# Board_3.net
KiCad netlist of a schematic drawn in EAGLE
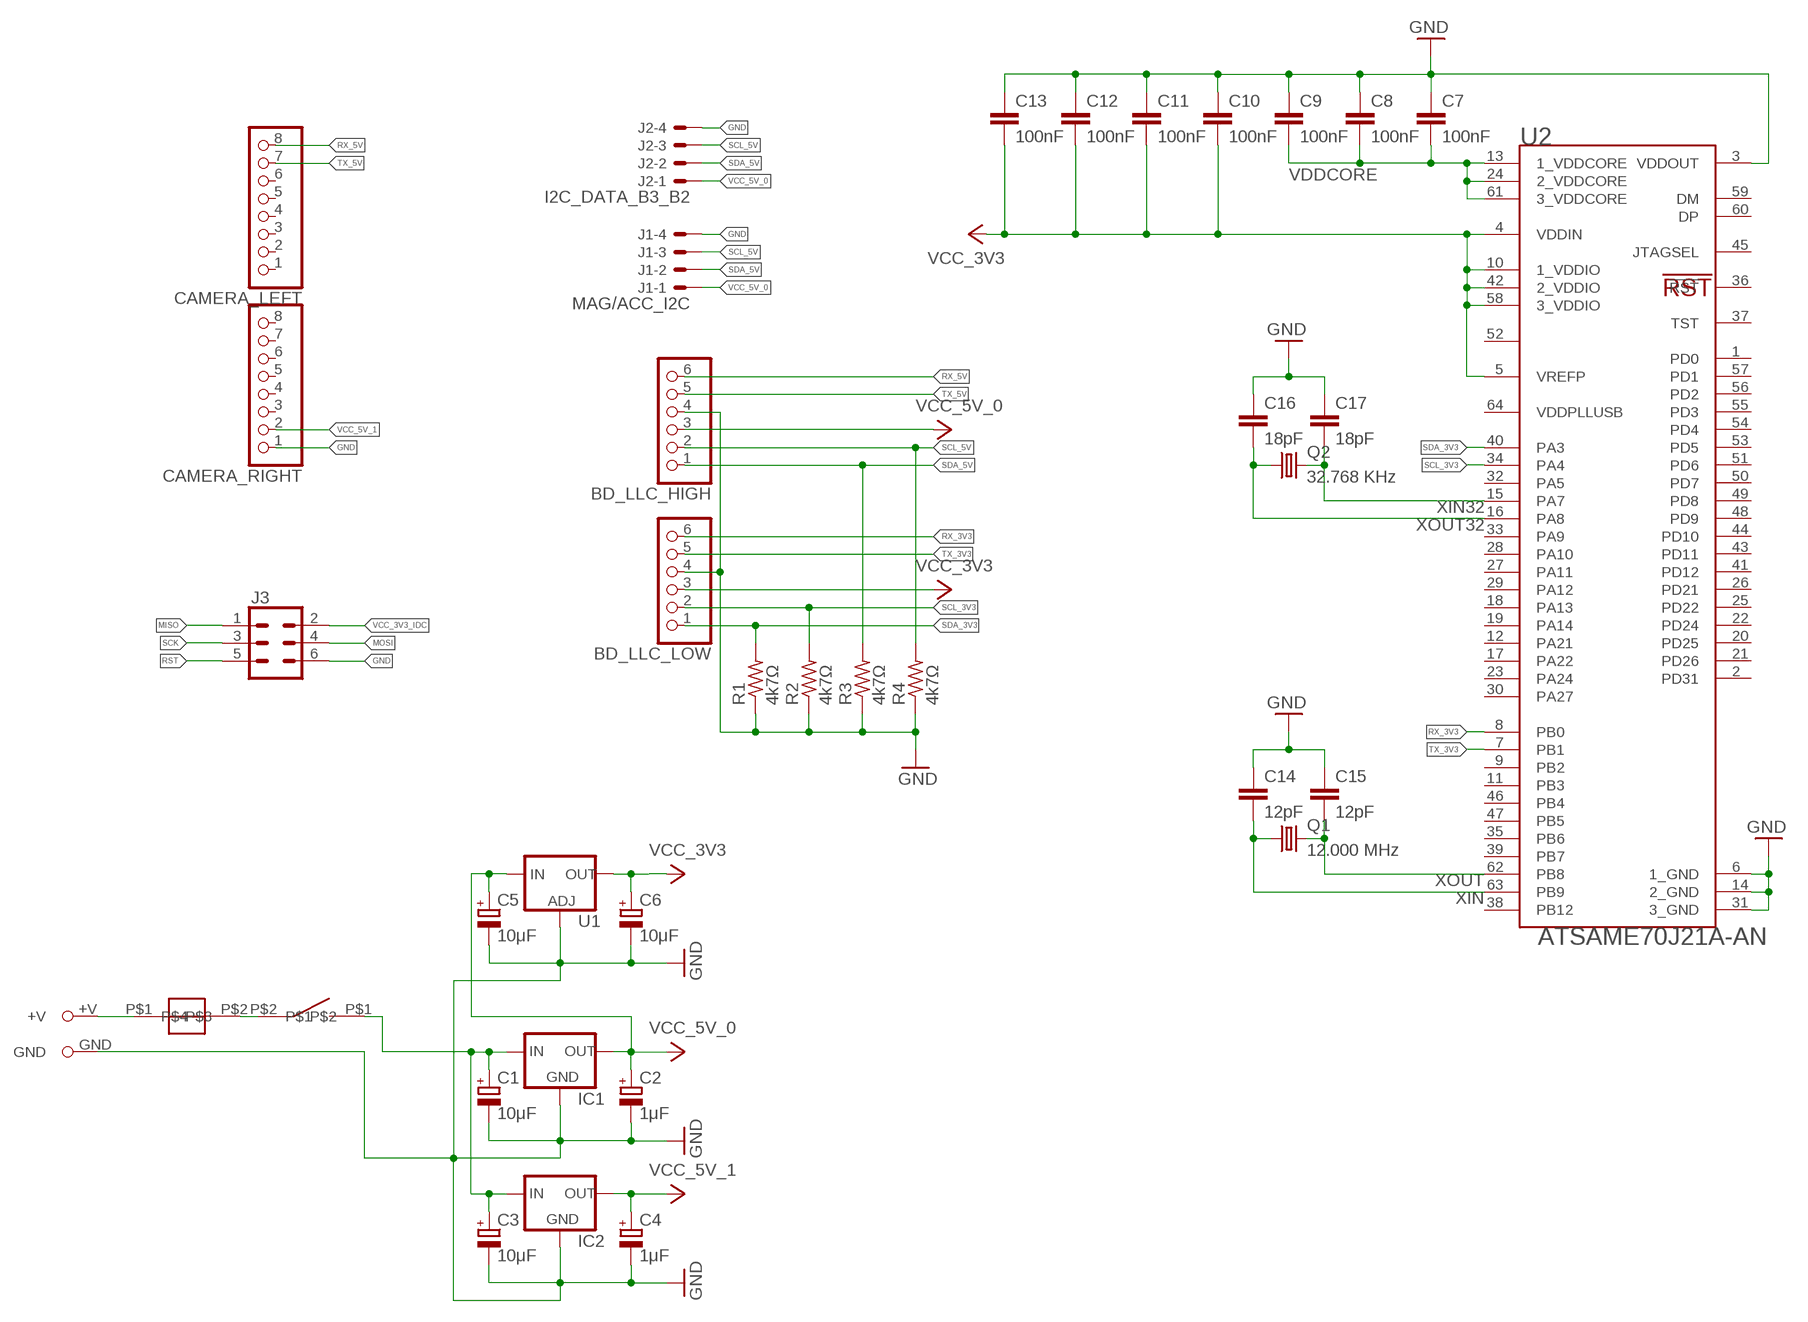
[diagram p0: schematic, sheet 1]

(export (version "E")
  (design (tool "Eeschema 10.0.6"))
  (components
    (comp (ref "BD_LLC_HIGH")
      (value "PINHD-1X6")
      (footprint "eagle-import:1X06")
      (libsource (lib "eagle-import") (part "PINHD-1X6"))
    )
    (comp (ref "BD_LLC_LOW")
      (value "PINHD-1X6")
      (footprint "eagle-import:1X06")
      (libsource (lib "eagle-import") (part "PINHD-1X6"))
    )
    (comp (ref "C1")
      (value "10μF")
      (footprint "eagle-import:E2-5")
      (libsource (lib "eagle-import") (part "CPOL-EUE2-5"))
    )
    (comp (ref "C2")
      (value "1μF")
      (footprint "eagle-import:E2-5")
      (libsource (lib "eagle-import") (part "CPOL-EUE2-5"))
    )
    (comp (ref "C3")
      (value "10μF")
      (footprint "eagle-import:E2-5")
      (libsource (lib "eagle-import") (part "CPOL-EUE2-5"))
    )
    (comp (ref "C4")
      (value "1μF")
      (footprint "eagle-import:E2-5")
      (libsource (lib "eagle-import") (part "CPOL-EUE2-5"))
    )
    (comp (ref "C5")
      (value "10μF")
      (footprint "eagle-import:E2-5")
      (libsource (lib "eagle-import") (part "CPOL-EUE2-5"))
    )
    (comp (ref "C6")
      (value "10μF")
      (footprint "eagle-import:E2-5")
      (libsource (lib "eagle-import") (part "CPOL-EUE2-5"))
    )
    (comp (ref "C7")
      (value "100nF")
      (footprint "eagle-import:C050-024X044")
      (libsource (lib "eagle-import") (part "C-EU050-024X044"))
    )
    (comp (ref "C8")
      (value "100nF")
      (footprint "eagle-import:C050-024X044")
      (libsource (lib "eagle-import") (part "C-EU050-024X044"))
    )
    (comp (ref "C9")
      (value "100nF")
      (footprint "eagle-import:C050-024X044")
      (libsource (lib "eagle-import") (part "C-EU050-024X044"))
    )
    (comp (ref "C10")
      (value "100nF")
      (footprint "eagle-import:C050-024X044")
      (libsource (lib "eagle-import") (part "C-EU050-024X044"))
    )
    (comp (ref "C11")
      (value "100nF")
      (footprint "eagle-import:C050-024X044")
      (libsource (lib "eagle-import") (part "C-EU050-024X044"))
    )
    (comp (ref "C12")
      (value "100nF")
      (footprint "eagle-import:C050-024X044")
      (libsource (lib "eagle-import") (part "C-EU050-024X044"))
    )
    (comp (ref "C13")
      (value "100nF")
      (footprint "eagle-import:C050-024X044")
      (libsource (lib "eagle-import") (part "C-EU050-024X044"))
    )
    (comp (ref "C14")
      (value "12pF")
      (footprint "eagle-import:C050-024X044")
      (libsource (lib "eagle-import") (part "C-EU050-024X044"))
    )
    (comp (ref "C15")
      (value "12pF")
      (footprint "eagle-import:C050-024X044")
      (libsource (lib "eagle-import") (part "C-EU050-024X044"))
    )
    (comp (ref "C16")
      (value "18pF")
      (footprint "eagle-import:C050-024X044")
      (libsource (lib "eagle-import") (part "C-EU050-024X044"))
    )
    (comp (ref "C17")
      (value "18pF")
      (footprint "eagle-import:C050-024X044")
      (libsource (lib "eagle-import") (part "C-EU050-024X044"))
    )
    (comp (ref "CAMERA_LEFT")
      (value "PINHD-1X8")
      (footprint "eagle-import:1X08")
      (libsource (lib "eagle-import") (part "PINHD-1X8"))
    )
    (comp (ref "CAMERA_RIGHT")
      (value "PINHD-1X8")
      (footprint "eagle-import:1X08")
      (libsource (lib "eagle-import") (part "PINHD-1X8"))
    )
    (comp (ref "IC1")
      (value "78XXS")
      (footprint "eagle-import:78XXS")
      (libsource (lib "eagle-import") (part "78XXS"))
    )
    (comp (ref "IC2")
      (value "78XXS")
      (footprint "eagle-import:78XXS")
      (libsource (lib "eagle-import") (part "78XXS"))
    )
    (comp (ref "J1")
      (value "MAG/ACC_I2C")
      (footprint "eagle-import:6410-04")
      (fields (field (name "MF") "MOLEX"))
      (libsource (lib "eagle-import") (part "22-?-0427-2041"))
    )
    (comp (ref "J2")
      (value "I2C_DATA_B3_B2")
      (footprint "eagle-import:6410-04")
      (fields (field (name "MF") "MOLEX"))
      (libsource (lib "eagle-import") (part "22-?-0427-2041"))
    )
    (comp (ref "J3")
      (value "CONN_03X2SHROUD")
      (footprint "eagle-import:2X3-SHROUDED")
      (libsource (lib "eagle-import") (part "CONN_03X2SHROUD"))
    )
    (comp (ref "Q1")
      (value "12.000 MHz")
      (footprint "eagle-import:HC49U-V")
      (libsource (lib "eagle-import") (part "crystal_204_CRYSTALHC49U-V"))
    )
    (comp (ref "Q2")
      (value "32.768 KHz")
      (footprint "eagle-import:TC26V")
      (libsource (lib "eagle-import") (part "CRYSTALTC26V"))
    )
    (comp (ref "R1")
      (value "4k7Ω")
      (footprint "eagle-import:0207_10")
      (libsource (lib "eagle-import") (part "R-US_0207/10"))
    )
    (comp (ref "R2")
      (value "4k7Ω")
      (footprint "eagle-import:0207_10")
      (libsource (lib "eagle-import") (part "R-US_0207/10"))
    )
    (comp (ref "R3")
      (value "4k7Ω")
      (footprint "eagle-import:0207_10")
      (libsource (lib "eagle-import") (part "R-US_0207/10"))
    )
    (comp (ref "R4")
      (value "4k7Ω")
      (footprint "eagle-import:0207_10")
      (libsource (lib "eagle-import") (part "R-US_0207/10"))
    )
    (comp (ref "SICHERUNG1")
      (value "SICHERUNG")
      (footprint "eagle-import:SICHERUNG")
      (libsource (lib "eagle-import") (part "SICHERUNG"))
    )
    (comp (ref "U$1")
      (value "XT60")
      (footprint "eagle-import:XT60")
      (libsource (lib "eagle-import") (part "XT60"))
    )
    (comp (ref "U$17")
      (value "SCHALTER")
      (footprint "eagle-import:SCHALTER")
      (libsource (lib "eagle-import") (part "SCHALTER"))
    )
    (comp (ref "U1")
      (value "V_REG_LM1117SOT223")
      (footprint "eagle-import:SOT223")
      (libsource (lib "eagle-import") (part "V_REG_LM1117SOT223"))
    )
    (comp (ref "U2")
      (value "ATMEL_CORPORATION_ATSAME70J21A-ANATMEL_CORPORATION_ATSAME70J21A-AN_0_0")
      (footprint "eagle-import:ATMEL_CORPORATION_ATSAME70J21A-AN_0")
      (fields
        (field (name "DIGIKEY_PART_NUMBER") "ATSAME70J21A-AN-ND")
        (field (name "MF") "Atmel Corporation")
        (field (name "MOUSER_PART_NUMBER") "556-ATSAME70J21A-AN")
      )
      (libsource (lib "eagle-import") (part "ATMEL_CORPORATION_ATSAME70J21A-ANATMEL_CORPORATION_ATSAME70J21A-AN_0_0"))
    )
  )
  (nets
    (net (code "1") (name "/VDDCORE") (class "Default")
      (node (ref "C7") (pin "2") (pinfunction "2_2") (pintype "passive"))
      (node (ref "C8") (pin "2") (pinfunction "2_2") (pintype "passive"))
      (node (ref "C9") (pin "2") (pinfunction "2_2") (pintype "passive"))
      (node (ref "U2") (pin "13") (pinfunction "1_VDDCORE_13") (pintype "bidirectional"))
      (node (ref "U2") (pin "24") (pinfunction "2_VDDCORE_24") (pintype "bidirectional"))
      (node (ref "U2") (pin "61") (pinfunction "3_VDDCORE_61") (pintype "bidirectional"))
    )
    (net (code "2") (name "/XIN") (class "Default")
      (node (ref "C14") (pin "2") (pinfunction "2_2") (pintype "passive"))
      (node (ref "Q1") (pin "1") (pinfunction "1_1") (pintype "passive"))
      (node (ref "U2") (pin "63") (pinfunction "PB9_63") (pintype "bidirectional"))
    )
    (net (code "3") (name "/XIN32") (class "Default")
      (node (ref "C17") (pin "2") (pinfunction "2_2") (pintype "passive"))
      (node (ref "Q2") (pin "2") (pinfunction "2_2") (pintype "passive"))
      (node (ref "U2") (pin "15") (pinfunction "PA7_15") (pintype "bidirectional"))
    )
    (net (code "4") (name "/XOUT") (class "Default")
      (node (ref "C15") (pin "2") (pinfunction "2_2") (pintype "passive"))
      (node (ref "Q1") (pin "2") (pinfunction "2_2") (pintype "passive"))
      (node (ref "U2") (pin "62") (pinfunction "PB8_62") (pintype "bidirectional"))
    )
    (net (code "5") (name "/XOUT32") (class "Default")
      (node (ref "C16") (pin "2") (pinfunction "2_2") (pintype "passive"))
      (node (ref "Q2") (pin "1") (pinfunction "1_1") (pintype "passive"))
      (node (ref "U2") (pin "16") (pinfunction "PA8_16") (pintype "bidirectional"))
    )
    (net (code "6") (name "GND") (class "Default")
      (node (ref "BD_LLC_HIGH") (pin "4") (pinfunction "4_4") (pintype "passive"))
      (node (ref "BD_LLC_LOW") (pin "4") (pinfunction "4_4") (pintype "passive"))
      (node (ref "C1") (pin "-") (pinfunction "-_-") (pintype "passive"))
      (node (ref "C10") (pin "1") (pinfunction "1_1") (pintype "passive"))
      (node (ref "C11") (pin "1") (pinfunction "1_1") (pintype "passive"))
      (node (ref "C12") (pin "1") (pinfunction "1_1") (pintype "passive"))
      (node (ref "C13") (pin "1") (pinfunction "1_1") (pintype "passive"))
      (node (ref "C14") (pin "1") (pinfunction "1_1") (pintype "passive"))
      (node (ref "C15") (pin "1") (pinfunction "1_1") (pintype "passive"))
      (node (ref "C16") (pin "1") (pinfunction "1_1") (pintype "passive"))
      (node (ref "C17") (pin "1") (pinfunction "1_1") (pintype "passive"))
      (node (ref "C2") (pin "-") (pinfunction "-_-") (pintype "passive"))
      (node (ref "C3") (pin "-") (pinfunction "-_-") (pintype "passive"))
      (node (ref "C4") (pin "-") (pinfunction "-_-") (pintype "passive"))
      (node (ref "C5") (pin "-") (pinfunction "-_-") (pintype "passive"))
      (node (ref "C6") (pin "-") (pinfunction "-_-") (pintype "passive"))
      (node (ref "C7") (pin "1") (pinfunction "1_1") (pintype "passive"))
      (node (ref "C8") (pin "1") (pinfunction "1_1") (pintype "passive"))
      (node (ref "C9") (pin "1") (pinfunction "1_1") (pintype "passive"))
      (node (ref "CAMERA_RIGHT") (pin "1") (pinfunction "1_1") (pintype "passive"))
      (node (ref "IC1") (pin "GND") (pinfunction "GND_GND") (pintype "input"))
      (node (ref "IC2") (pin "GND") (pinfunction "GND_GND") (pintype "input"))
      (node (ref "J1") (pin "4") (pinfunction "S_4") (pintype "passive"))
      (node (ref "J2") (pin "4") (pinfunction "S_4") (pintype "passive"))
      (node (ref "J3") (pin "6") (pinfunction "6_6") (pintype "bidirectional"))
      (node (ref "R1") (pin "1") (pinfunction "1_1") (pintype "passive"))
      (node (ref "R2") (pin "1") (pinfunction "1_1") (pintype "passive"))
      (node (ref "R3") (pin "1") (pinfunction "1_1") (pintype "passive"))
      (node (ref "R4") (pin "1") (pinfunction "1_1") (pintype "passive"))
      (node (ref "U$1") (pin "GND") (pinfunction "GND_GND") (pintype "bidirectional"))
      (node (ref "U1") (pin "1") (pinfunction "ADJ_1") (pintype "input"))
      (node (ref "U2") (pin "14") (pinfunction "2_GND_14") (pintype "bidirectional"))
      (node (ref "U2") (pin "3") (pinfunction "VDDOUT_3") (pintype "bidirectional"))
      (node (ref "U2") (pin "31") (pinfunction "3_GND_31") (pintype "bidirectional"))
      (node (ref "U2") (pin "6") (pinfunction "1_GND_6") (pintype "bidirectional"))
    )
    (net (code "7") (name "MISO") (class "Default")
      (node (ref "J3") (pin "1") (pinfunction "1_1") (pintype "bidirectional"))
    )
    (net (code "8") (name "MOSI") (class "Default")
      (node (ref "J3") (pin "4") (pinfunction "4_4") (pintype "bidirectional"))
    )
    (net (code "9") (name "Net-(C1-Pad+)") (class "Default")
      (node (ref "C1") (pin "+") (pinfunction "+_+") (pintype "passive"))
      (node (ref "C3") (pin "+") (pinfunction "+_+") (pintype "passive"))
      (node (ref "IC1") (pin "IN") (pinfunction "IN_IN") (pintype "input"))
      (node (ref "IC2") (pin "IN") (pinfunction "IN_IN") (pintype "input"))
      (node (ref "U$17") (pin "P$1") (pinfunction "P$1_P$1") (pintype "bidirectional"))
    )
    (net (code "10") (name "Net-(SICHERUNG1-P$3)") (class "Default")
      (node (ref "SICHERUNG1") (pin "P$1") (pinfunction "P$3_P$1") (pintype "bidirectional"))
      (node (ref "U$1") (pin "+V") (pinfunction "+V_+V") (pintype "bidirectional"))
    )
    (net (code "11") (name "Net-(SICHERUNG1-P$4)") (class "Default")
      (node (ref "SICHERUNG1") (pin "P$2") (pinfunction "P$4_P$2") (pintype "bidirectional"))
      (node (ref "U$17") (pin "P$2") (pinfunction "P$2_P$2") (pintype "bidirectional"))
    )
    (net (code "12") (name "RST") (class "Default")
      (node (ref "J3") (pin "5") (pinfunction "5_5") (pintype "bidirectional"))
    )
    (net (code "13") (name "RX_3V3") (class "Default")
      (node (ref "BD_LLC_LOW") (pin "6") (pinfunction "6_6") (pintype "passive"))
      (node (ref "U2") (pin "8") (pinfunction "PB0_8") (pintype "bidirectional"))
    )
    (net (code "14") (name "RX_5V") (class "Default")
      (node (ref "BD_LLC_HIGH") (pin "6") (pinfunction "6_6") (pintype "passive"))
      (node (ref "CAMERA_LEFT") (pin "8") (pinfunction "8_8") (pintype "passive"))
    )
    (net (code "15") (name "SCK") (class "Default")
      (node (ref "J3") (pin "3") (pinfunction "3_3") (pintype "bidirectional"))
    )
    (net (code "16") (name "SCL_3V3") (class "Default")
      (node (ref "BD_LLC_LOW") (pin "2") (pinfunction "2_2") (pintype "passive"))
      (node (ref "R2") (pin "2") (pinfunction "2_2") (pintype "passive"))
      (node (ref "U2") (pin "34") (pinfunction "PA4_34") (pintype "bidirectional"))
    )
    (net (code "17") (name "SCL_5V") (class "Default")
      (node (ref "BD_LLC_HIGH") (pin "2") (pinfunction "2_2") (pintype "passive"))
      (node (ref "J1") (pin "3") (pinfunction "S_3") (pintype "passive"))
      (node (ref "J2") (pin "3") (pinfunction "S_3") (pintype "passive"))
      (node (ref "R4") (pin "2") (pinfunction "2_2") (pintype "passive"))
    )
    (net (code "18") (name "SDA_3V3") (class "Default")
      (node (ref "BD_LLC_LOW") (pin "1") (pinfunction "1_1") (pintype "passive"))
      (node (ref "R1") (pin "2") (pinfunction "2_2") (pintype "passive"))
      (node (ref "U2") (pin "40") (pinfunction "PA3_40") (pintype "bidirectional"))
    )
    (net (code "19") (name "SDA_5V") (class "Default")
      (node (ref "BD_LLC_HIGH") (pin "1") (pinfunction "1_1") (pintype "passive"))
      (node (ref "J1") (pin "2") (pinfunction "S_2") (pintype "passive"))
      (node (ref "J2") (pin "2") (pinfunction "S_2") (pintype "passive"))
      (node (ref "R3") (pin "2") (pinfunction "2_2") (pintype "passive"))
    )
    (net (code "20") (name "TX_3V3") (class "Default")
      (node (ref "BD_LLC_LOW") (pin "5") (pinfunction "5_5") (pintype "passive"))
      (node (ref "U2") (pin "7") (pinfunction "PB1_7") (pintype "bidirectional"))
    )
    (net (code "21") (name "TX_5V") (class "Default")
      (node (ref "BD_LLC_HIGH") (pin "5") (pinfunction "5_5") (pintype "passive"))
      (node (ref "CAMERA_LEFT") (pin "7") (pinfunction "7_7") (pintype "passive"))
    )
    (net (code "22") (name "VCC_3V3") (class "Default")
      (node (ref "BD_LLC_LOW") (pin "3") (pinfunction "3_3") (pintype "passive"))
      (node (ref "C10") (pin "2") (pinfunction "2_2") (pintype "passive"))
      (node (ref "C11") (pin "2") (pinfunction "2_2") (pintype "passive"))
      (node (ref "C12") (pin "2") (pinfunction "2_2") (pintype "passive"))
      (node (ref "C13") (pin "2") (pinfunction "2_2") (pintype "passive"))
      (node (ref "C6") (pin "+") (pinfunction "+_+") (pintype "passive"))
      (node (ref "U1") (pin "2") (pinfunction "OUT_2") (pintype "output"))
      (node (ref "U1") (pin "4") (pinfunction "OUT_4") (pintype "output"))
      (node (ref "U2") (pin "10") (pinfunction "1_VDDIO_10") (pintype "bidirectional"))
      (node (ref "U2") (pin "4") (pinfunction "VDDIN_4") (pintype "bidirectional"))
      (node (ref "U2") (pin "42") (pinfunction "2_VDDIO_42") (pintype "bidirectional"))
      (node (ref "U2") (pin "5") (pinfunction "VREFP_5") (pintype "bidirectional"))
      (node (ref "U2") (pin "58") (pinfunction "3_VDDIO_58") (pintype "bidirectional"))
    )
    (net (code "23") (name "VCC_3V3_IDC") (class "Default")
      (node (ref "J3") (pin "2") (pinfunction "2_2") (pintype "bidirectional"))
    )
    (net (code "24") (name "VCC_5V_0") (class "Default")
      (node (ref "BD_LLC_HIGH") (pin "3") (pinfunction "3_3") (pintype "passive"))
      (node (ref "C2") (pin "+") (pinfunction "+_+") (pintype "passive"))
      (node (ref "C5") (pin "+") (pinfunction "+_+") (pintype "passive"))
      (node (ref "IC1") (pin "OUT") (pinfunction "OUT_OUT") (pintype "passive"))
      (node (ref "J1") (pin "1") (pinfunction "S_1") (pintype "passive"))
      (node (ref "J2") (pin "1") (pinfunction "S_1") (pintype "passive"))
      (node (ref "U1") (pin "3") (pinfunction "IN_3") (pintype "input"))
    )
    (net (code "25") (name "VCC_5V_1") (class "Default")
      (node (ref "C4") (pin "+") (pinfunction "+_+") (pintype "passive"))
      (node (ref "CAMERA_RIGHT") (pin "2") (pinfunction "2_2") (pintype "passive"))
      (node (ref "IC2") (pin "OUT") (pinfunction "OUT_OUT") (pintype "passive"))
    )
    (net (code "26") (name "unconnected-(CAMERA_LEFT-Pad1)") (class "Default")
      (node (ref "CAMERA_LEFT") (pin "1") (pinfunction "1_1") (pintype "passive"))
    )
    (net (code "27") (name "unconnected-(CAMERA_LEFT-Pad2)") (class "Default")
      (node (ref "CAMERA_LEFT") (pin "2") (pinfunction "2_2") (pintype "passive"))
    )
    (net (code "28") (name "unconnected-(CAMERA_LEFT-Pad3)") (class "Default")
      (node (ref "CAMERA_LEFT") (pin "3") (pinfunction "3_3") (pintype "passive"))
    )
    (net (code "29") (name "unconnected-(CAMERA_LEFT-Pad4)") (class "Default")
      (node (ref "CAMERA_LEFT") (pin "4") (pinfunction "4_4") (pintype "passive"))
    )
    (net (code "30") (name "unconnected-(CAMERA_LEFT-Pad5)") (class "Default")
      (node (ref "CAMERA_LEFT") (pin "5") (pinfunction "5_5") (pintype "passive"))
    )
    (net (code "31") (name "unconnected-(CAMERA_LEFT-Pad6)") (class "Default")
      (node (ref "CAMERA_LEFT") (pin "6") (pinfunction "6_6") (pintype "passive"))
    )
    (net (code "32") (name "unconnected-(CAMERA_RIGHT-Pad3)") (class "Default")
      (node (ref "CAMERA_RIGHT") (pin "3") (pinfunction "3_3") (pintype "passive"))
    )
    (net (code "33") (name "unconnected-(CAMERA_RIGHT-Pad4)") (class "Default")
      (node (ref "CAMERA_RIGHT") (pin "4") (pinfunction "4_4") (pintype "passive"))
    )
    (net (code "34") (name "unconnected-(CAMERA_RIGHT-Pad5)") (class "Default")
      (node (ref "CAMERA_RIGHT") (pin "5") (pinfunction "5_5") (pintype "passive"))
    )
    (net (code "35") (name "unconnected-(CAMERA_RIGHT-Pad6)") (class "Default")
      (node (ref "CAMERA_RIGHT") (pin "6") (pinfunction "6_6") (pintype "passive"))
    )
    (net (code "36") (name "unconnected-(CAMERA_RIGHT-Pad7)") (class "Default")
      (node (ref "CAMERA_RIGHT") (pin "7") (pinfunction "7_7") (pintype "passive"))
    )
    (net (code "37") (name "unconnected-(CAMERA_RIGHT-Pad8)") (class "Default")
      (node (ref "CAMERA_RIGHT") (pin "8") (pinfunction "8_8") (pintype "passive"))
    )
    (net (code "38") (name "unconnected-(U2-DM-Pad59)") (class "Default")
      (node (ref "U2") (pin "59") (pinfunction "DM_59") (pintype "bidirectional"))
    )
    (net (code "39") (name "unconnected-(U2-DP-Pad60)") (class "Default")
      (node (ref "U2") (pin "60") (pinfunction "DP_60") (pintype "bidirectional"))
    )
    (net (code "40") (name "unconnected-(U2-JTAGSEL-Pad45)") (class "Default")
      (node (ref "U2") (pin "45") (pinfunction "JTAGSEL_45") (pintype "bidirectional"))
    )
    (net (code "41") (name "unconnected-(U2-PA5-Pad32)") (class "Default")
      (node (ref "U2") (pin "32") (pinfunction "PA5_32") (pintype "bidirectional"))
    )
    (net (code "42") (name "unconnected-(U2-PA9-Pad33)") (class "Default")
      (node (ref "U2") (pin "33") (pinfunction "PA9_33") (pintype "bidirectional"))
    )
    (net (code "43") (name "unconnected-(U2-PA10-Pad28)") (class "Default")
      (node (ref "U2") (pin "28") (pinfunction "PA10_28") (pintype "bidirectional"))
    )
    (net (code "44") (name "unconnected-(U2-PA11-Pad27)") (class "Default")
      (node (ref "U2") (pin "27") (pinfunction "PA11_27") (pintype "bidirectional"))
    )
    (net (code "45") (name "unconnected-(U2-PA12-Pad29)") (class "Default")
      (node (ref "U2") (pin "29") (pinfunction "PA12_29") (pintype "bidirectional"))
    )
    (net (code "46") (name "unconnected-(U2-PA13-Pad18)") (class "Default")
      (node (ref "U2") (pin "18") (pinfunction "PA13_18") (pintype "bidirectional"))
    )
    (net (code "47") (name "unconnected-(U2-PA14-Pad19)") (class "Default")
      (node (ref "U2") (pin "19") (pinfunction "PA14_19") (pintype "bidirectional"))
    )
    (net (code "48") (name "unconnected-(U2-PA21-Pad12)") (class "Default")
      (node (ref "U2") (pin "12") (pinfunction "PA21_12") (pintype "bidirectional"))
    )
    (net (code "49") (name "unconnected-(U2-PA22-Pad17)") (class "Default")
      (node (ref "U2") (pin "17") (pinfunction "PA22_17") (pintype "bidirectional"))
    )
    (net (code "50") (name "unconnected-(U2-PA24-Pad23)") (class "Default")
      (node (ref "U2") (pin "23") (pinfunction "PA24_23") (pintype "bidirectional"))
    )
    (net (code "51") (name "unconnected-(U2-PA27-Pad30)") (class "Default")
      (node (ref "U2") (pin "30") (pinfunction "PA27_30") (pintype "bidirectional"))
    )
    (net (code "52") (name "unconnected-(U2-PB2-Pad9)") (class "Default")
      (node (ref "U2") (pin "9") (pinfunction "PB2_9") (pintype "bidirectional"))
    )
    (net (code "53") (name "unconnected-(U2-PB3-Pad11)") (class "Default")
      (node (ref "U2") (pin "11") (pinfunction "PB3_11") (pintype "bidirectional"))
    )
    (net (code "54") (name "unconnected-(U2-PB4-Pad46)") (class "Default")
      (node (ref "U2") (pin "46") (pinfunction "PB4_46") (pintype "bidirectional"))
    )
    (net (code "55") (name "unconnected-(U2-PB5-Pad47)") (class "Default")
      (node (ref "U2") (pin "47") (pinfunction "PB5_47") (pintype "bidirectional"))
    )
    (net (code "56") (name "unconnected-(U2-PB6-Pad35)") (class "Default")
      (node (ref "U2") (pin "35") (pinfunction "PB6_35") (pintype "bidirectional"))
    )
    (net (code "57") (name "unconnected-(U2-PB7-Pad39)") (class "Default")
      (node (ref "U2") (pin "39") (pinfunction "PB7_39") (pintype "bidirectional"))
    )
    (net (code "58") (name "unconnected-(U2-PB12-Pad38)") (class "Default")
      (node (ref "U2") (pin "38") (pinfunction "PB12_38") (pintype "bidirectional"))
    )
    (net (code "59") (name "unconnected-(U2-PD0-Pad1)") (class "Default")
      (node (ref "U2") (pin "1") (pinfunction "PD0_1") (pintype "bidirectional"))
    )
    (net (code "60") (name "unconnected-(U2-PD1-Pad57)") (class "Default")
      (node (ref "U2") (pin "57") (pinfunction "PD1_57") (pintype "bidirectional"))
    )
    (net (code "61") (name "unconnected-(U2-PD2-Pad56)") (class "Default")
      (node (ref "U2") (pin "56") (pinfunction "PD2_56") (pintype "bidirectional"))
    )
    (net (code "62") (name "unconnected-(U2-PD3-Pad55)") (class "Default")
      (node (ref "U2") (pin "55") (pinfunction "PD3_55") (pintype "bidirectional"))
    )
    (net (code "63") (name "unconnected-(U2-PD4-Pad54)") (class "Default")
      (node (ref "U2") (pin "54") (pinfunction "PD4_54") (pintype "bidirectional"))
    )
    (net (code "64") (name "unconnected-(U2-PD5-Pad53)") (class "Default")
      (node (ref "U2") (pin "53") (pinfunction "PD5_53") (pintype "bidirectional"))
    )
    (net (code "65") (name "unconnected-(U2-PD6-Pad51)") (class "Default")
      (node (ref "U2") (pin "51") (pinfunction "PD6_51") (pintype "bidirectional"))
    )
    (net (code "66") (name "unconnected-(U2-PD7-Pad50)") (class "Default")
      (node (ref "U2") (pin "50") (pinfunction "PD7_50") (pintype "bidirectional"))
    )
    (net (code "67") (name "unconnected-(U2-PD8-Pad49)") (class "Default")
      (node (ref "U2") (pin "49") (pinfunction "PD8_49") (pintype "bidirectional"))
    )
    (net (code "68") (name "unconnected-(U2-PD9-Pad48)") (class "Default")
      (node (ref "U2") (pin "48") (pinfunction "PD9_48") (pintype "bidirectional"))
    )
    (net (code "69") (name "unconnected-(U2-PD10-Pad44)") (class "Default")
      (node (ref "U2") (pin "44") (pinfunction "PD10_44") (pintype "bidirectional"))
    )
    (net (code "70") (name "unconnected-(U2-PD11-Pad43)") (class "Default")
      (node (ref "U2") (pin "43") (pinfunction "PD11_43") (pintype "bidirectional"))
    )
    (net (code "71") (name "unconnected-(U2-PD12-Pad41)") (class "Default")
      (node (ref "U2") (pin "41") (pinfunction "PD12_41") (pintype "bidirectional"))
    )
    (net (code "72") (name "unconnected-(U2-PD21-Pad26)") (class "Default")
      (node (ref "U2") (pin "26") (pinfunction "PD21_26") (pintype "bidirectional"))
    )
    (net (code "73") (name "unconnected-(U2-PD22-Pad25)") (class "Default")
      (node (ref "U2") (pin "25") (pinfunction "PD22_25") (pintype "bidirectional"))
    )
    (net (code "74") (name "unconnected-(U2-PD24-Pad22)") (class "Default")
      (node (ref "U2") (pin "22") (pinfunction "PD24_22") (pintype "bidirectional"))
    )
    (net (code "75") (name "unconnected-(U2-PD25-Pad20)") (class "Default")
      (node (ref "U2") (pin "20") (pinfunction "PD25_20") (pintype "bidirectional"))
    )
    (net (code "76") (name "unconnected-(U2-PD26-Pad21)") (class "Default")
      (node (ref "U2") (pin "21") (pinfunction "PD26_21") (pintype "bidirectional"))
    )
    (net (code "77") (name "unconnected-(U2-PD31-Pad2)") (class "Default")
      (node (ref "U2") (pin "2") (pinfunction "PD31_2") (pintype "bidirectional"))
    )
    (net (code "78") (name "unconnected-(U2-TST-Pad37)") (class "Default")
      (node (ref "U2") (pin "37") (pinfunction "TST_37") (pintype "bidirectional"))
    )
    (net (code "79") (name "unconnected-(U2-VDDPLL-Pad52)") (class "Default")
      (node (ref "U2") (pin "52") (pinfunction "VDDPLL_52") (pintype "bidirectional"))
    )
    (net (code "80") (name "unconnected-(U2-VDDPLLUSB-Pad64)") (class "Default")
      (node (ref "U2") (pin "64") (pinfunction "VDDPLLUSB_64") (pintype "bidirectional"))
    )
    (net (code "81") (name "unconnected-(U2-~{RST}-Pad36)") (class "Default")
      (node (ref "U2") (pin "36") (pinfunction "~{RST}_36") (pintype "bidirectional"))
    )
  )
)
